# Oxygen_Sensor_CO2_PWM.net
KiCad netlist of a schematic drawn in EAGLE
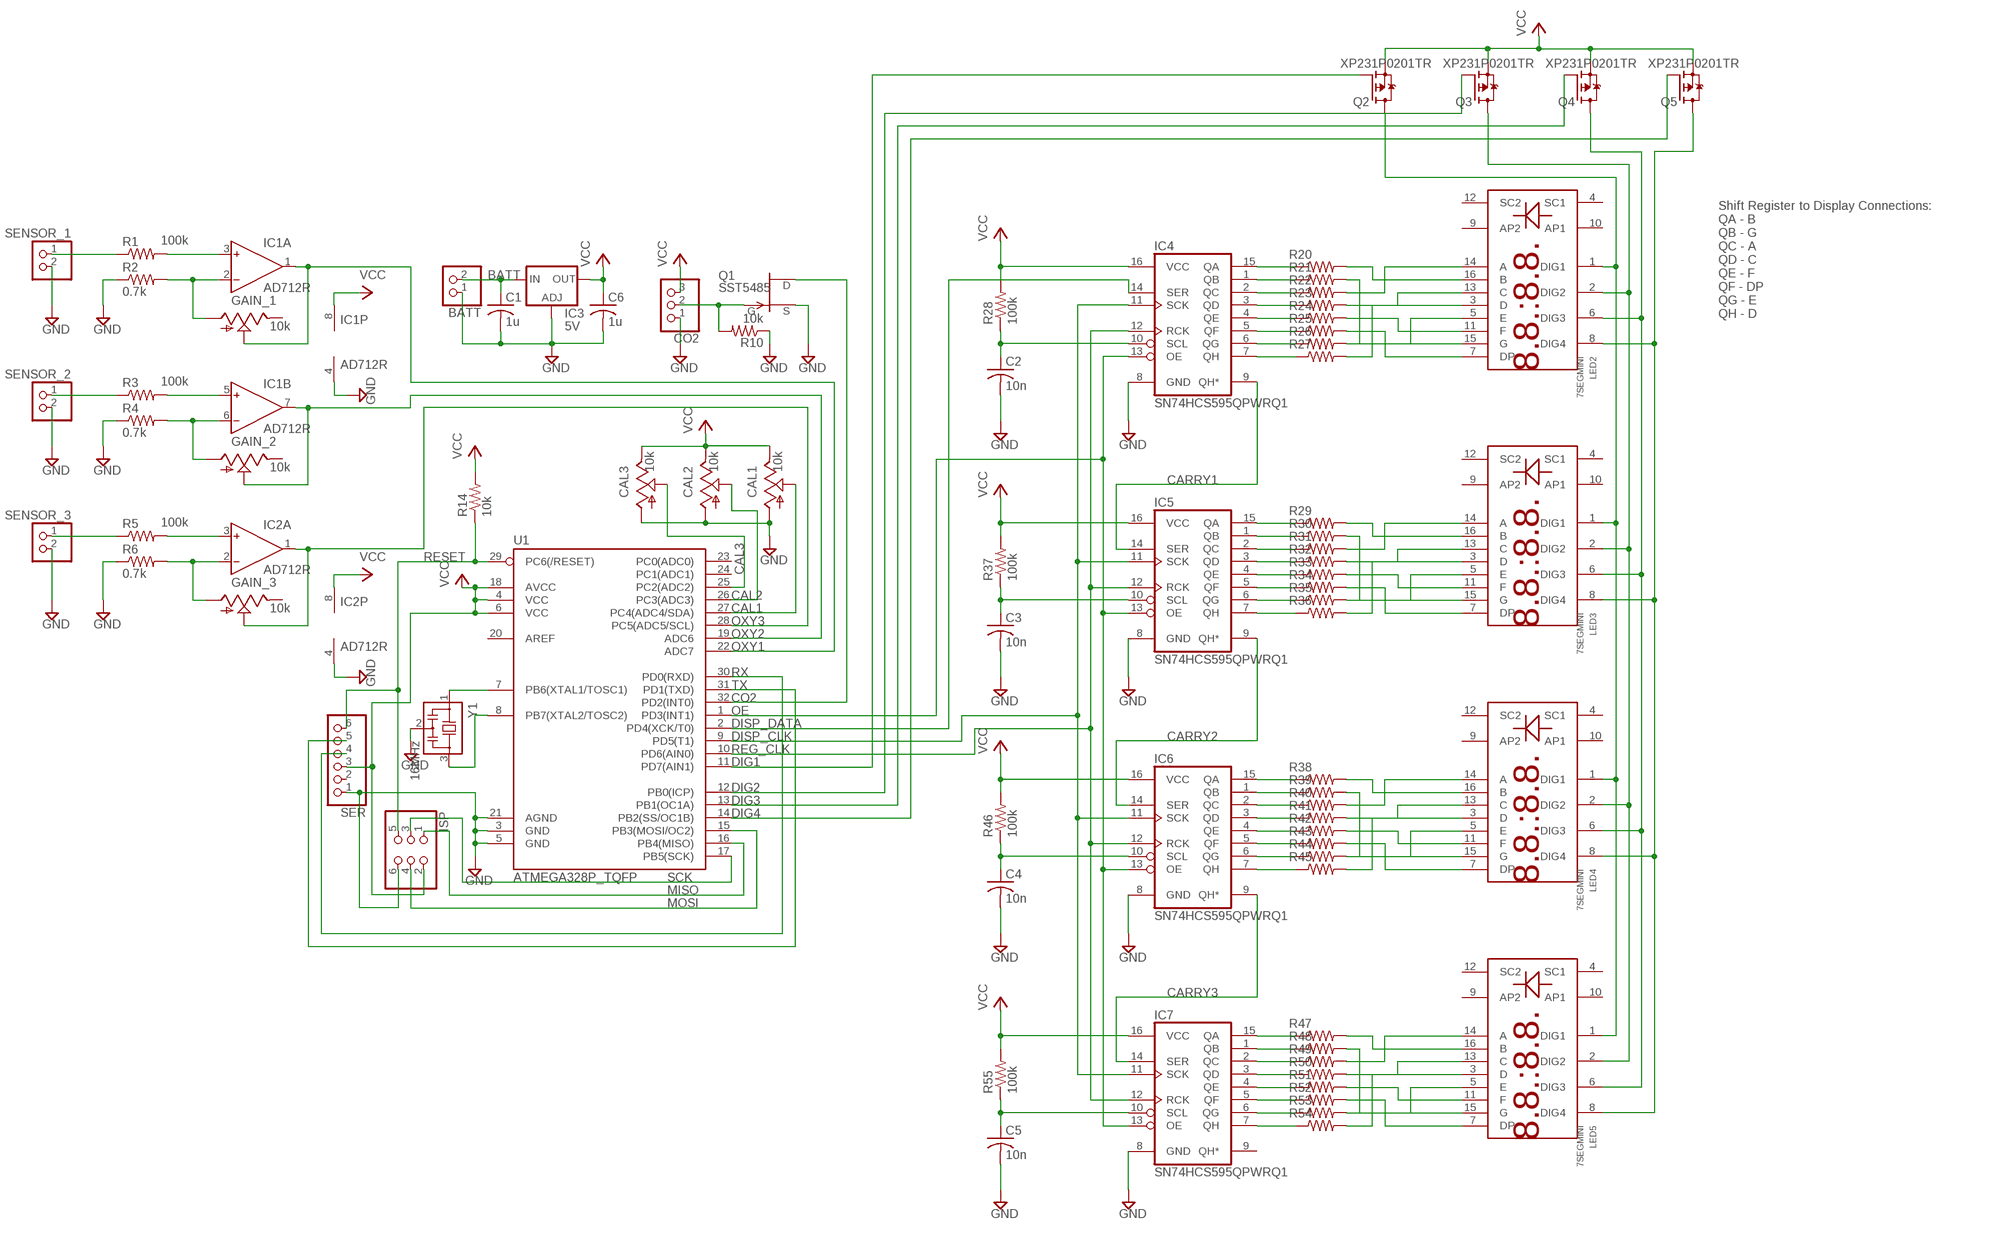
[diagram p0: schematic, sheet 1]

(export (version "E")
  (design (tool "Eeschema 10.0.6"))
  (components
    (comp (ref "BATT")
      (value "BATT")
      (footprint "eagle-import:1X02")
      (libsource (lib "eagle-import") (part "PINHD-1X2"))
    )
    (comp (ref "C1")
      (value "1u")
      (footprint "eagle-import:C0603")
      (libsource (lib "eagle-import") (part "C-USC0603"))
    )
    (comp (ref "C2")
      (value "10n")
      (footprint "eagle-import:C0603")
      (libsource (lib "eagle-import") (part "C-USC0603"))
    )
    (comp (ref "C3")
      (value "10n")
      (footprint "eagle-import:C0603")
      (libsource (lib "eagle-import") (part "C-USC0603"))
    )
    (comp (ref "C4")
      (value "10n")
      (footprint "eagle-import:C0603")
      (libsource (lib "eagle-import") (part "C-USC0603"))
    )
    (comp (ref "C5")
      (value "10n")
      (footprint "eagle-import:C0603")
      (libsource (lib "eagle-import") (part "C-USC0603"))
    )
    (comp (ref "C6")
      (value "1u")
      (footprint "eagle-import:C0603")
      (libsource (lib "eagle-import") (part "C-USC0603"))
    )
    (comp (ref "CAL1")
      (value "10k")
      (footprint "eagle-import:RJ9W")
      (libsource (lib "eagle-import") (part "TRIM_US-RJ9W"))
    )
    (comp (ref "CAL2")
      (value "10k")
      (footprint "eagle-import:RJ9W")
      (libsource (lib "eagle-import") (part "TRIM_US-RJ9W"))
    )
    (comp (ref "CAL3")
      (value "10k")
      (footprint "eagle-import:RJ9W")
      (libsource (lib "eagle-import") (part "TRIM_US-RJ9W"))
    )
    (comp (ref "CO2")
      (value "CO2")
      (footprint "eagle-import:1X03")
      (libsource (lib "eagle-import") (part "PINHD-1X3"))
    )
    (comp (ref "GAIN_1")
      (value "10k")
      (footprint "eagle-import:RJ9W")
      (libsource (lib "eagle-import") (part "TRIM_US-RJ9W"))
    )
    (comp (ref "GAIN_2")
      (value "10k")
      (footprint "eagle-import:RJ9W")
      (libsource (lib "eagle-import") (part "TRIM_US-RJ9W"))
    )
    (comp (ref "GAIN_3")
      (value "10k")
      (footprint "eagle-import:RJ9W")
      (libsource (lib "eagle-import") (part "TRIM_US-RJ9W"))
    )
    (comp (ref "IC1")
      (value "AD712R")
      (footprint "eagle-import:SO8")
      (fields (field (name "MF") "ALTERA CORPORATION") (field (name "MPN") "AD712KRZ"))
      (libsource (lib "eagle-import") (part "AD712R"))
    )
    (comp (ref "IC2")
      (value "AD712R")
      (footprint "eagle-import:SO8")
      (fields (field (name "MF") "ALTERA CORPORATION") (field (name "MPN") "AD712KRZ"))
      (libsource (lib "eagle-import") (part "AD712R"))
    )
    (comp (ref "IC3")
      (value "5V")
      (footprint "eagle-import:SOT223")
      (libsource (lib "eagle-import") (part "LD117A?STR"))
    )
    (comp (ref "IC4")
      (value "SN74HCS595QPWRQ1")
      (footprint "eagle-import:TSSOP16")
      (libsource (lib "eagle-import") (part "SN74HCS595QPWRQ1"))
    )
    (comp (ref "IC5")
      (value "SN74HCS595QPWRQ1")
      (footprint "eagle-import:TSSOP16")
      (libsource (lib "eagle-import") (part "SN74HCS595QPWRQ1"))
    )
    (comp (ref "IC6")
      (value "SN74HCS595QPWRQ1")
      (footprint "eagle-import:TSSOP16")
      (libsource (lib "eagle-import") (part "SN74HCS595QPWRQ1"))
    )
    (comp (ref "IC7")
      (value "SN74HCS595QPWRQ1")
      (footprint "eagle-import:TSSOP16")
      (libsource (lib "eagle-import") (part "SN74HCS595QPWRQ1"))
    )
    (comp (ref "ISP")
      (value "ISP")
      (footprint "eagle-import:2X03")
      (libsource (lib "eagle-import") (part "PINHD-2X3"))
    )
    (comp (ref "LED2")
      (value "7SEGMINI")
      (footprint "eagle-import:7SEGMINI")
      (libsource (lib "eagle-import") (part "7SEGMINI"))
    )
    (comp (ref "LED3")
      (value "7SEGMINI")
      (footprint "eagle-import:7SEGMINI")
      (libsource (lib "eagle-import") (part "7SEGMINI"))
    )
    (comp (ref "LED4")
      (value "7SEGMINI")
      (footprint "eagle-import:7SEGMINI")
      (libsource (lib "eagle-import") (part "7SEGMINI"))
    )
    (comp (ref "LED5")
      (value "7SEGMINI")
      (footprint "eagle-import:7SEGMINI")
      (libsource (lib "eagle-import") (part "7SEGMINI"))
    )
    (comp (ref "Q1")
      (value "SST5485")
      (footprint "eagle-import:SOT23")
      (libsource (lib "eagle-import") (part "?548SST5"))
    )
    (comp (ref "Q2")
      (value "XP231P0201TR")
      (footprint "eagle-import:SOT23")
      (libsource (lib "eagle-import") (part "XP231P0201TR"))
    )
    (comp (ref "Q3")
      (value "XP231P0201TR")
      (footprint "eagle-import:SOT23")
      (libsource (lib "eagle-import") (part "XP231P0201TR"))
    )
    (comp (ref "Q4")
      (value "XP231P0201TR")
      (footprint "eagle-import:SOT23")
      (libsource (lib "eagle-import") (part "XP231P0201TR"))
    )
    (comp (ref "Q5")
      (value "XP231P0201TR")
      (footprint "eagle-import:SOT23")
      (libsource (lib "eagle-import") (part "XP231P0201TR"))
    )
    (comp (ref "R1")
      (value "100k")
      (footprint "eagle-import:R0603")
      (libsource (lib "eagle-import") (part "R-US_R0603"))
    )
    (comp (ref "R2")
      (value "0.7k")
      (footprint "eagle-import:R0603")
      (libsource (lib "eagle-import") (part "R-US_R0603"))
    )
    (comp (ref "R3")
      (value "100k")
      (footprint "eagle-import:R0603")
      (libsource (lib "eagle-import") (part "R-US_R0603"))
    )
    (comp (ref "R4")
      (value "0.7k")
      (footprint "eagle-import:R0603")
      (libsource (lib "eagle-import") (part "R-US_R0603"))
    )
    (comp (ref "R5")
      (value "100k")
      (footprint "eagle-import:R0603")
      (libsource (lib "eagle-import") (part "R-US_R0603"))
    )
    (comp (ref "R6")
      (value "0.7k")
      (footprint "eagle-import:R0603")
      (libsource (lib "eagle-import") (part "R-US_R0603"))
    )
    (comp (ref "R10")
      (value "10k")
      (footprint "eagle-import:R0603")
      (libsource (lib "eagle-import") (part "R-US_R0603"))
    )
    (comp (ref "R14")
      (value "10k")
      (footprint "eagle-import:R0603")
      (libsource (lib "eagle-import") (part "R-US_R0603"))
    )
    (comp (ref "R20")
      (value "R-US_R0603")
      (footprint "eagle-import:R0603")
      (libsource (lib "eagle-import") (part "R-US_R0603"))
    )
    (comp (ref "R21")
      (value "R-US_R0603")
      (footprint "eagle-import:R0603")
      (libsource (lib "eagle-import") (part "R-US_R0603"))
    )
    (comp (ref "R22")
      (value "R-US_R0603")
      (footprint "eagle-import:R0603")
      (libsource (lib "eagle-import") (part "R-US_R0603"))
    )
    (comp (ref "R23")
      (value "R-US_R0603")
      (footprint "eagle-import:R0603")
      (libsource (lib "eagle-import") (part "R-US_R0603"))
    )
    (comp (ref "R24")
      (value "R-US_R0603")
      (footprint "eagle-import:R0603")
      (libsource (lib "eagle-import") (part "R-US_R0603"))
    )
    (comp (ref "R25")
      (value "R-US_R0603")
      (footprint "eagle-import:R0603")
      (libsource (lib "eagle-import") (part "R-US_R0603"))
    )
    (comp (ref "R26")
      (value "R-US_R0603")
      (footprint "eagle-import:R0603")
      (libsource (lib "eagle-import") (part "R-US_R0603"))
    )
    (comp (ref "R27")
      (value "R-US_R0603")
      (footprint "eagle-import:R0603")
      (libsource (lib "eagle-import") (part "R-US_R0603"))
    )
    (comp (ref "R28")
      (value "100k")
      (footprint "eagle-import:R0603")
      (libsource (lib "eagle-import") (part "R-US_R0603"))
    )
    (comp (ref "R29")
      (value "R-US_R0603")
      (footprint "eagle-import:R0603")
      (libsource (lib "eagle-import") (part "R-US_R0603"))
    )
    (comp (ref "R30")
      (value "R-US_R0603")
      (footprint "eagle-import:R0603")
      (libsource (lib "eagle-import") (part "R-US_R0603"))
    )
    (comp (ref "R31")
      (value "R-US_R0603")
      (footprint "eagle-import:R0603")
      (libsource (lib "eagle-import") (part "R-US_R0603"))
    )
    (comp (ref "R32")
      (value "R-US_R0603")
      (footprint "eagle-import:R0603")
      (libsource (lib "eagle-import") (part "R-US_R0603"))
    )
    (comp (ref "R33")
      (value "R-US_R0603")
      (footprint "eagle-import:R0603")
      (libsource (lib "eagle-import") (part "R-US_R0603"))
    )
    (comp (ref "R34")
      (value "R-US_R0603")
      (footprint "eagle-import:R0603")
      (libsource (lib "eagle-import") (part "R-US_R0603"))
    )
    (comp (ref "R35")
      (value "R-US_R0603")
      (footprint "eagle-import:R0603")
      (libsource (lib "eagle-import") (part "R-US_R0603"))
    )
    (comp (ref "R36")
      (value "R-US_R0603")
      (footprint "eagle-import:R0603")
      (libsource (lib "eagle-import") (part "R-US_R0603"))
    )
    (comp (ref "R37")
      (value "100k")
      (footprint "eagle-import:R0603")
      (libsource (lib "eagle-import") (part "R-US_R0603"))
    )
    (comp (ref "R38")
      (value "R-US_R0603")
      (footprint "eagle-import:R0603")
      (libsource (lib "eagle-import") (part "R-US_R0603"))
    )
    (comp (ref "R39")
      (value "R-US_R0603")
      (footprint "eagle-import:R0603")
      (libsource (lib "eagle-import") (part "R-US_R0603"))
    )
    (comp (ref "R40")
      (value "R-US_R0603")
      (footprint "eagle-import:R0603")
      (libsource (lib "eagle-import") (part "R-US_R0603"))
    )
    (comp (ref "R41")
      (value "R-US_R0603")
      (footprint "eagle-import:R0603")
      (libsource (lib "eagle-import") (part "R-US_R0603"))
    )
    (comp (ref "R42")
      (value "R-US_R0603")
      (footprint "eagle-import:R0603")
      (libsource (lib "eagle-import") (part "R-US_R0603"))
    )
    (comp (ref "R43")
      (value "R-US_R0603")
      (footprint "eagle-import:R0603")
      (libsource (lib "eagle-import") (part "R-US_R0603"))
    )
    (comp (ref "R44")
      (value "R-US_R0603")
      (footprint "eagle-import:R0603")
      (libsource (lib "eagle-import") (part "R-US_R0603"))
    )
    (comp (ref "R45")
      (value "R-US_R0603")
      (footprint "eagle-import:R0603")
      (libsource (lib "eagle-import") (part "R-US_R0603"))
    )
    (comp (ref "R46")
      (value "100k")
      (footprint "eagle-import:R0603")
      (libsource (lib "eagle-import") (part "R-US_R0603"))
    )
    (comp (ref "R47")
      (value "R-US_R0603")
      (footprint "eagle-import:R0603")
      (libsource (lib "eagle-import") (part "R-US_R0603"))
    )
    (comp (ref "R48")
      (value "R-US_R0603")
      (footprint "eagle-import:R0603")
      (libsource (lib "eagle-import") (part "R-US_R0603"))
    )
    (comp (ref "R49")
      (value "R-US_R0603")
      (footprint "eagle-import:R0603")
      (libsource (lib "eagle-import") (part "R-US_R0603"))
    )
    (comp (ref "R50")
      (value "R-US_R0603")
      (footprint "eagle-import:R0603")
      (libsource (lib "eagle-import") (part "R-US_R0603"))
    )
    (comp (ref "R51")
      (value "R-US_R0603")
      (footprint "eagle-import:R0603")
      (libsource (lib "eagle-import") (part "R-US_R0603"))
    )
    (comp (ref "R52")
      (value "R-US_R0603")
      (footprint "eagle-import:R0603")
      (libsource (lib "eagle-import") (part "R-US_R0603"))
    )
    (comp (ref "R53")
      (value "R-US_R0603")
      (footprint "eagle-import:R0603")
      (libsource (lib "eagle-import") (part "R-US_R0603"))
    )
    (comp (ref "R54")
      (value "R-US_R0603")
      (footprint "eagle-import:R0603")
      (libsource (lib "eagle-import") (part "R-US_R0603"))
    )
    (comp (ref "R55")
      (value "100k")
      (footprint "eagle-import:R0603")
      (libsource (lib "eagle-import") (part "R-US_R0603"))
    )
    (comp (ref "SENSOR_1")
      (value "PINHD-1X2")
      (footprint "eagle-import:1X02")
      (libsource (lib "eagle-import") (part "PINHD-1X2"))
    )
    (comp (ref "SENSOR_2")
      (value "PINHD-1X2")
      (footprint "eagle-import:1X02")
      (libsource (lib "eagle-import") (part "PINHD-1X2"))
    )
    (comp (ref "SENSOR_3")
      (value "PINHD-1X2")
      (footprint "eagle-import:1X02")
      (libsource (lib "eagle-import") (part "PINHD-1X2"))
    )
    (comp (ref "SER")
      (value "SER")
      (footprint "eagle-import:1X06")
      (libsource (lib "eagle-import") (part "PINHD-1X6"))
    )
    (comp (ref "U1")
      (value "ATMEGA328P_TQFP")
      (footprint "eagle-import:TQFP32-08")
      (libsource (lib "eagle-import") (part "ATMEGA328P_TQFP"))
    )
    (comp (ref "Y1")
      (value "16MHz")
      (footprint "eagle-import:CSTCR6M")
      (libsource (lib "eagle-import") (part "CSTNE16M0V530000R0"))
    )
  )
  (nets
    (net (code "1") (name "/BATT") (class "Default")
      (node (ref "BATT") (pin "2") (pinfunction "2_2") (pintype "passive"))
      (node (ref "C1") (pin "1") (pinfunction "1_1") (pintype "passive"))
      (node (ref "IC3") (pin "3") (pinfunction "IN_3") (pintype "input"))
    )
    (net (code "2") (name "/CAL1") (class "Default")
      (node (ref "CAL1") (pin "S") (pinfunction "S_S") (pintype "passive"))
      (node (ref "U1") (pin "27") (pinfunction "PC4(ADC4/SDA)_27") (pintype "bidirectional"))
    )
    (net (code "3") (name "/CAL2") (class "Default")
      (node (ref "CAL2") (pin "S") (pinfunction "S_S") (pintype "passive"))
      (node (ref "U1") (pin "26") (pinfunction "PC3(ADC3)_26") (pintype "bidirectional"))
    )
    (net (code "4") (name "/CAL3") (class "Default")
      (node (ref "CAL3") (pin "S") (pinfunction "S_S") (pintype "passive"))
      (node (ref "U1") (pin "25") (pinfunction "PC2(ADC2)_25") (pintype "bidirectional"))
    )
    (net (code "5") (name "/CARRY1") (class "Default")
      (node (ref "IC4") (pin "9") (pinfunction "QH*_9") (pintype "tri_state"))
      (node (ref "IC5") (pin "14") (pinfunction "SER_14") (pintype "input"))
    )
    (net (code "6") (name "/CARRY2") (class "Default")
      (node (ref "IC5") (pin "9") (pinfunction "QH*_9") (pintype "tri_state"))
      (node (ref "IC6") (pin "14") (pinfunction "SER_14") (pintype "input"))
    )
    (net (code "7") (name "/CARRY3") (class "Default")
      (node (ref "IC6") (pin "9") (pinfunction "QH*_9") (pintype "tri_state"))
      (node (ref "IC7") (pin "14") (pinfunction "SER_14") (pintype "input"))
    )
    (net (code "8") (name "/CO2") (class "Default")
      (node (ref "Q1") (pin "1") (pinfunction "D_1") (pintype "passive"))
      (node (ref "U1") (pin "32") (pinfunction "PD2(INT0)_32") (pintype "bidirectional"))
    )
    (net (code "9") (name "/DIG1") (class "Default")
      (node (ref "Q2") (pin "1") (pinfunction "G_1") (pintype "passive"))
      (node (ref "U1") (pin "11") (pinfunction "PD7(AIN1)_11") (pintype "bidirectional"))
    )
    (net (code "10") (name "/DIG2") (class "Default")
      (node (ref "Q3") (pin "1") (pinfunction "G_1") (pintype "passive"))
      (node (ref "U1") (pin "12") (pinfunction "PB0(ICP)_12") (pintype "bidirectional"))
    )
    (net (code "11") (name "/DIG3") (class "Default")
      (node (ref "Q4") (pin "1") (pinfunction "G_1") (pintype "passive"))
      (node (ref "U1") (pin "13") (pinfunction "PB1(OC1A)_13") (pintype "bidirectional"))
    )
    (net (code "12") (name "/DIG4") (class "Default")
      (node (ref "Q5") (pin "1") (pinfunction "G_1") (pintype "passive"))
      (node (ref "U1") (pin "14") (pinfunction "PB2(SS/OC1B)_14") (pintype "bidirectional"))
    )
    (net (code "13") (name "/DISP_CLK") (class "Default")
      (node (ref "IC4") (pin "11") (pinfunction "SCK_11") (pintype "input"))
      (node (ref "IC5") (pin "11") (pinfunction "SCK_11") (pintype "input"))
      (node (ref "IC6") (pin "11") (pinfunction "SCK_11") (pintype "input"))
      (node (ref "IC7") (pin "11") (pinfunction "SCK_11") (pintype "input"))
      (node (ref "U1") (pin "9") (pinfunction "PD5(T1)_9") (pintype "bidirectional"))
    )
    (net (code "14") (name "/DISP_DATA") (class "Default")
      (node (ref "IC4") (pin "14") (pinfunction "SER_14") (pintype "input"))
      (node (ref "U1") (pin "2") (pinfunction "PD4(XCK/T0)_2") (pintype "bidirectional"))
    )
    (net (code "15") (name "/MISO") (class "Default")
      (node (ref "ISP") (pin "1") (pinfunction "1_1") (pintype "passive"))
      (node (ref "U1") (pin "16") (pinfunction "PB4(MISO)_16") (pintype "bidirectional"))
    )
    (net (code "16") (name "/MOSI") (class "Default")
      (node (ref "ISP") (pin "4") (pinfunction "4_4") (pintype "passive"))
      (node (ref "U1") (pin "15") (pinfunction "PB3(MOSI/OC2)_15") (pintype "bidirectional"))
    )
    (net (code "17") (name "/OE") (class "Default")
      (node (ref "IC4") (pin "13") (pinfunction "OE_13") (pintype "bidirectional"))
      (node (ref "IC5") (pin "13") (pinfunction "OE_13") (pintype "bidirectional"))
      (node (ref "IC6") (pin "13") (pinfunction "OE_13") (pintype "bidirectional"))
      (node (ref "IC7") (pin "13") (pinfunction "OE_13") (pintype "bidirectional"))
      (node (ref "U1") (pin "1") (pinfunction "PD3(INT1)_1") (pintype "bidirectional"))
    )
    (net (code "18") (name "/OXY1") (class "Default")
      (node (ref "GAIN_1") (pin "S") (pinfunction "S_S") (pintype "passive"))
      (node (ref "IC1") (pin "1") (pinfunction "OUT_1") (pintype "output"))
      (node (ref "U1") (pin "22") (pinfunction "ADC7_22") (pintype "bidirectional"))
    )
    (net (code "19") (name "/OXY2") (class "Default")
      (node (ref "GAIN_2") (pin "S") (pinfunction "S_S") (pintype "passive"))
      (node (ref "IC1") (pin "7") (pinfunction "OUT_7") (pintype "output"))
      (node (ref "U1") (pin "19") (pinfunction "ADC6_19") (pintype "bidirectional"))
    )
    (net (code "20") (name "/OXY3") (class "Default")
      (node (ref "GAIN_3") (pin "S") (pinfunction "S_S") (pintype "passive"))
      (node (ref "IC2") (pin "1") (pinfunction "OUT_1") (pintype "output"))
      (node (ref "U1") (pin "28") (pinfunction "PC5(ADC5/SCL)_28") (pintype "bidirectional"))
    )
    (net (code "21") (name "/REG_CLK") (class "Default")
      (node (ref "IC4") (pin "12") (pinfunction "RCK_12") (pintype "input"))
      (node (ref "IC5") (pin "12") (pinfunction "RCK_12") (pintype "input"))
      (node (ref "IC6") (pin "12") (pinfunction "RCK_12") (pintype "input"))
      (node (ref "IC7") (pin "12") (pinfunction "RCK_12") (pintype "input"))
      (node (ref "U1") (pin "10") (pinfunction "PD6(AIN0)_10") (pintype "bidirectional"))
    )
    (net (code "22") (name "/RESET") (class "Default")
      (node (ref "ISP") (pin "5") (pinfunction "5_5") (pintype "passive"))
      (node (ref "R14") (pin "1") (pinfunction "1_1") (pintype "passive"))
      (node (ref "SER") (pin "6") (pinfunction "6_6") (pintype "passive"))
      (node (ref "U1") (pin "29") (pinfunction "PC6(/RESET)_29") (pintype "bidirectional"))
    )
    (net (code "23") (name "/RX") (class "Default")
      (node (ref "SER") (pin "4") (pinfunction "4_4") (pintype "passive"))
      (node (ref "U1") (pin "30") (pinfunction "PD0(RXD)_30") (pintype "bidirectional"))
    )
    (net (code "24") (name "/SCK") (class "Default")
      (node (ref "ISP") (pin "3") (pinfunction "3_3") (pintype "passive"))
      (node (ref "U1") (pin "17") (pinfunction "PB5(SCK)_17") (pintype "bidirectional"))
    )
    (net (code "25") (name "/TX") (class "Default")
      (node (ref "SER") (pin "5") (pinfunction "5_5") (pintype "passive"))
      (node (ref "U1") (pin "31") (pinfunction "PD1(TXD)_31") (pintype "bidirectional"))
    )
    (net (code "26") (name "GND") (class "Default")
      (node (ref "BATT") (pin "1") (pinfunction "1_1") (pintype "passive"))
      (node (ref "C1") (pin "2") (pinfunction "2_2") (pintype "passive"))
      (node (ref "C2") (pin "2") (pinfunction "2_2") (pintype "passive"))
      (node (ref "C3") (pin "2") (pinfunction "2_2") (pintype "passive"))
      (node (ref "C4") (pin "2") (pinfunction "2_2") (pintype "passive"))
      (node (ref "C5") (pin "2") (pinfunction "2_2") (pintype "passive"))
      (node (ref "C6") (pin "2") (pinfunction "2_2") (pintype "passive"))
      (node (ref "CAL1") (pin "A") (pinfunction "A_A") (pintype "passive"))
      (node (ref "CAL2") (pin "A") (pinfunction "A_A") (pintype "passive"))
      (node (ref "CAL3") (pin "A") (pinfunction "A_A") (pintype "passive"))
      (node (ref "CO2") (pin "1") (pinfunction "1_1") (pintype "passive"))
      (node (ref "IC1") (pin "4") (pinfunction "V-_4") (pintype "power_in"))
      (node (ref "IC2") (pin "4") (pinfunction "V-_4") (pintype "power_in"))
      (node (ref "IC3") (pin "1") (pinfunction "ADJ_1") (pintype "input"))
      (node (ref "IC4") (pin "8") (pinfunction "GND_8") (pintype "power_in"))
      (node (ref "IC5") (pin "8") (pinfunction "GND_8") (pintype "power_in"))
      (node (ref "IC6") (pin "8") (pinfunction "GND_8") (pintype "power_in"))
      (node (ref "IC7") (pin "8") (pinfunction "GND_8") (pintype "power_in"))
      (node (ref "ISP") (pin "6") (pinfunction "6_6") (pintype "passive"))
      (node (ref "Q1") (pin "2") (pinfunction "S_2") (pintype "passive"))
      (node (ref "R10") (pin "1") (pinfunction "1_1") (pintype "passive"))
      (node (ref "R2") (pin "1") (pinfunction "1_1") (pintype "passive"))
      (node (ref "R4") (pin "1") (pinfunction "1_1") (pintype "passive"))
      (node (ref "R6") (pin "1") (pinfunction "1_1") (pintype "passive"))
      (node (ref "SENSOR_1") (pin "2") (pinfunction "2_2") (pintype "passive"))
      (node (ref "SENSOR_2") (pin "2") (pinfunction "2_2") (pintype "passive"))
      (node (ref "SENSOR_3") (pin "2") (pinfunction "2_2") (pintype "passive"))
      (node (ref "SER") (pin "1") (pinfunction "1_1") (pintype "passive"))
      (node (ref "U1") (pin "21") (pinfunction "AGND_21") (pintype "bidirectional"))
      (node (ref "U1") (pin "3") (pinfunction "GND_3") (pintype "bidirectional"))
      (node (ref "U1") (pin "5") (pinfunction "GND_5") (pintype "bidirectional"))
      (node (ref "Y1") (pin "2") (pinfunction "2_2") (pintype "passive"))
    )
    (net (code "27") (name "Net-(IC1A-IN+)") (class "Default")
      (node (ref "IC1") (pin "3") (pinfunction "IN+_3") (pintype "input"))
      (node (ref "R1") (pin "2") (pinfunction "2_2") (pintype "passive"))
    )
    (net (code "28") (name "Net-(IC1A-IN-)") (class "Default")
      (node (ref "GAIN_1") (pin "A") (pinfunction "A_A") (pintype "passive"))
      (node (ref "IC1") (pin "2") (pinfunction "IN-_2") (pintype "input"))
      (node (ref "R2") (pin "2") (pinfunction "2_2") (pintype "passive"))
    )
    (net (code "29") (name "Net-(IC1B-IN+)") (class "Default")
      (node (ref "IC1") (pin "5") (pinfunction "IN+_5") (pintype "input"))
      (node (ref "R3") (pin "2") (pinfunction "2_2") (pintype "passive"))
    )
    (net (code "30") (name "Net-(IC1B-IN-)") (class "Default")
      (node (ref "GAIN_2") (pin "A") (pinfunction "A_A") (pintype "passive"))
      (node (ref "IC1") (pin "6") (pinfunction "IN-_6") (pintype "input"))
      (node (ref "R4") (pin "2") (pinfunction "2_2") (pintype "passive"))
    )
    (net (code "31") (name "Net-(IC2A-IN+)") (class "Default")
      (node (ref "IC2") (pin "3") (pinfunction "IN+_3") (pintype "input"))
      (node (ref "R5") (pin "2") (pinfunction "2_2") (pintype "passive"))
    )
    (net (code "32") (name "Net-(IC2A-IN-)") (class "Default")
      (node (ref "GAIN_3") (pin "A") (pinfunction "A_A") (pintype "passive"))
      (node (ref "IC2") (pin "2") (pinfunction "IN-_2") (pintype "input"))
      (node (ref "R6") (pin "2") (pinfunction "2_2") (pintype "passive"))
    )
    (net (code "33") (name "Net-(IC4-QA)") (class "Default")
      (node (ref "IC4") (pin "15") (pinfunction "QA_15") (pintype "tri_state"))
      (node (ref "R20") (pin "1") (pinfunction "1_1") (pintype "passive"))
    )
    (net (code "34") (name "Net-(IC4-QB)") (class "Default")
      (node (ref "IC4") (pin "1") (pinfunction "QB_1") (pintype "tri_state"))
      (node (ref "R21") (pin "1") (pinfunction "1_1") (pintype "passive"))
    )
    (net (code "35") (name "Net-(IC4-QC)") (class "Default")
      (node (ref "IC4") (pin "2") (pinfunction "QC_2") (pintype "tri_state"))
      (node (ref "R22") (pin "1") (pinfunction "1_1") (pintype "passive"))
    )
    (net (code "36") (name "Net-(IC4-QD)") (class "Default")
      (node (ref "IC4") (pin "3") (pinfunction "QD_3") (pintype "tri_state"))
      (node (ref "R23") (pin "1") (pinfunction "1_1") (pintype "passive"))
    )
    (net (code "37") (name "Net-(IC4-QE)") (class "Default")
      (node (ref "IC4") (pin "4") (pinfunction "QE_4") (pintype "tri_state"))
      (node (ref "R24") (pin "1") (pinfunction "1_1") (pintype "passive"))
    )
    (net (code "38") (name "Net-(IC4-QF)") (class "Default")
      (node (ref "IC4") (pin "5") (pinfunction "QF_5") (pintype "tri_state"))
      (node (ref "R25") (pin "1") (pinfunction "1_1") (pintype "passive"))
    )
    (net (code "39") (name "Net-(IC4-QG)") (class "Default")
      (node (ref "IC4") (pin "6") (pinfunction "QG_6") (pintype "tri_state"))
      (node (ref "R26") (pin "1") (pinfunction "1_1") (pintype "passive"))
    )
    (net (code "40") (name "Net-(IC4-QH)") (class "Default")
      (node (ref "IC4") (pin "7") (pinfunction "QH_7") (pintype "tri_state"))
      (node (ref "R27") (pin "1") (pinfunction "1_1") (pintype "passive"))
    )
    (net (code "41") (name "Net-(IC4-SCL)") (class "Default")
      (node (ref "C2") (pin "1") (pinfunction "1_1") (pintype "passive"))
      (node (ref "IC4") (pin "10") (pinfunction "SCL_10") (pintype "input"))
      (node (ref "R28") (pin "1") (pinfunction "1_1") (pintype "passive"))
    )
    (net (code "42") (name "Net-(IC5-QA)") (class "Default")
      (node (ref "IC5") (pin "15") (pinfunction "QA_15") (pintype "tri_state"))
      (node (ref "R29") (pin "1") (pinfunction "1_1") (pintype "passive"))
    )
    (net (code "43") (name "Net-(IC5-QB)") (class "Default")
      (node (ref "IC5") (pin "1") (pinfunction "QB_1") (pintype "tri_state"))
      (node (ref "R30") (pin "1") (pinfunction "1_1") (pintype "passive"))
    )
    (net (code "44") (name "Net-(IC5-QC)") (class "Default")
      (node (ref "IC5") (pin "2") (pinfunction "QC_2") (pintype "tri_state"))
      (node (ref "R31") (pin "1") (pinfunction "1_1") (pintype "passive"))
    )
    (net (code "45") (name "Net-(IC5-QD)") (class "Default")
      (node (ref "IC5") (pin "3") (pinfunction "QD_3") (pintype "tri_state"))
      (node (ref "R32") (pin "1") (pinfunction "1_1") (pintype "passive"))
    )
    (net (code "46") (name "Net-(IC5-QE)") (class "Default")
      (node (ref "IC5") (pin "4") (pinfunction "QE_4") (pintype "tri_state"))
      (node (ref "R33") (pin "1") (pinfunction "1_1") (pintype "passive"))
    )
    (net (code "47") (name "Net-(IC5-QF)") (class "Default")
      (node (ref "IC5") (pin "5") (pinfunction "QF_5") (pintype "tri_state"))
      (node (ref "R34") (pin "1") (pinfunction "1_1") (pintype "passive"))
    )
    (net (code "48") (name "Net-(IC5-QG)") (class "Default")
      (node (ref "IC5") (pin "6") (pinfunction "QG_6") (pintype "tri_state"))
      (node (ref "R35") (pin "1") (pinfunction "1_1") (pintype "passive"))
    )
    (net (code "49") (name "Net-(IC5-QH)") (class "Default")
      (node (ref "IC5") (pin "7") (pinfunction "QH_7") (pintype "tri_state"))
      (node (ref "R36") (pin "1") (pinfunction "1_1") (pintype "passive"))
    )
    (net (code "50") (name "Net-(IC5-SCL)") (class "Default")
      (node (ref "C3") (pin "1") (pinfunction "1_1") (pintype "passive"))
      (node (ref "IC5") (pin "10") (pinfunction "SCL_10") (pintype "input"))
      (node (ref "R37") (pin "1") (pinfunction "1_1") (pintype "passive"))
    )
    (net (code "51") (name "Net-(IC6-QA)") (class "Default")
      (node (ref "IC6") (pin "15") (pinfunction "QA_15") (pintype "tri_state"))
      (node (ref "R38") (pin "1") (pinfunction "1_1") (pintype "passive"))
    )
    (net (code "52") (name "Net-(IC6-QB)") (class "Default")
      (node (ref "IC6") (pin "1") (pinfunction "QB_1") (pintype "tri_state"))
      (node (ref "R39") (pin "1") (pinfunction "1_1") (pintype "passive"))
    )
    (net (code "53") (name "Net-(IC6-QC)") (class "Default")
      (node (ref "IC6") (pin "2") (pinfunction "QC_2") (pintype "tri_state"))
      (node (ref "R40") (pin "1") (pinfunction "1_1") (pintype "passive"))
    )
    (net (code "54") (name "Net-(IC6-QD)") (class "Default")
      (node (ref "IC6") (pin "3") (pinfunction "QD_3") (pintype "tri_state"))
      (node (ref "R41") (pin "1") (pinfunction "1_1") (pintype "passive"))
    )
    (net (code "55") (name "Net-(IC6-QE)") (class "Default")
      (node (ref "IC6") (pin "4") (pinfunction "QE_4") (pintype "tri_state"))
      (node (ref "R42") (pin "1") (pinfunction "1_1") (pintype "passive"))
    )
    (net (code "56") (name "Net-(IC6-QF)") (class "Default")
      (node (ref "IC6") (pin "5") (pinfunction "QF_5") (pintype "tri_state"))
      (node (ref "R43") (pin "1") (pinfunction "1_1") (pintype "passive"))
    )
    (net (code "57") (name "Net-(IC6-QG)") (class "Default")
      (node (ref "IC6") (pin "6") (pinfunction "QG_6") (pintype "tri_state"))
      (node (ref "R44") (pin "1") (pinfunction "1_1") (pintype "passive"))
    )
    (net (code "58") (name "Net-(IC6-QH)") (class "Default")
      (node (ref "IC6") (pin "7") (pinfunction "QH_7") (pintype "tri_state"))
      (node (ref "R45") (pin "1") (pinfunction "1_1") (pintype "passive"))
    )
    (net (code "59") (name "Net-(IC6-SCL)") (class "Default")
      (node (ref "C4") (pin "1") (pinfunction "1_1") (pintype "passive"))
      (node (ref "IC6") (pin "10") (pinfunction "SCL_10") (pintype "input"))
      (node (ref "R46") (pin "1") (pinfunction "1_1") (pintype "passive"))
    )
    (net (code "60") (name "Net-(IC7-QA)") (class "Default")
      (node (ref "IC7") (pin "15") (pinfunction "QA_15") (pintype "tri_state"))
      (node (ref "R47") (pin "1") (pinfunction "1_1") (pintype "passive"))
    )
    (net (code "61") (name "Net-(IC7-QB)") (class "Default")
      (node (ref "IC7") (pin "1") (pinfunction "QB_1") (pintype "tri_state"))
      (node (ref "R48") (pin "1") (pinfunction "1_1") (pintype "passive"))
    )
    (net (code "62") (name "Net-(IC7-QC)") (class "Default")
      (node (ref "IC7") (pin "2") (pinfunction "QC_2") (pintype "tri_state"))
      (node (ref "R49") (pin "1") (pinfunction "1_1") (pintype "passive"))
    )
    (net (code "63") (name "Net-(IC7-QD)") (class "Default")
      (node (ref "IC7") (pin "3") (pinfunction "QD_3") (pintype "tri_state"))
      (node (ref "R50") (pin "1") (pinfunction "1_1") (pintype "passive"))
    )
    (net (code "64") (name "Net-(IC7-QE)") (class "Default")
      (node (ref "IC7") (pin "4") (pinfunction "QE_4") (pintype "tri_state"))
      (node (ref "R51") (pin "1") (pinfunction "1_1") (pintype "passive"))
    )
    (net (code "65") (name "Net-(IC7-QF)") (class "Default")
      (node (ref "IC7") (pin "5") (pinfunction "QF_5") (pintype "tri_state"))
      (node (ref "R52") (pin "1") (pinfunction "1_1") (pintype "passive"))
    )
    (net (code "66") (name "Net-(IC7-QG)") (class "Default")
      (node (ref "IC7") (pin "6") (pinfunction "QG_6") (pintype "tri_state"))
      (node (ref "R53") (pin "1") (pinfunction "1_1") (pintype "passive"))
    )
    (net (code "67") (name "Net-(IC7-QH)") (class "Default")
      (node (ref "IC7") (pin "7") (pinfunction "QH_7") (pintype "tri_state"))
      (node (ref "R54") (pin "1") (pinfunction "1_1") (pintype "passive"))
    )
    (net (code "68") (name "Net-(IC7-SCL)") (class "Default")
      (node (ref "C5") (pin "1") (pinfunction "1_1") (pintype "passive"))
      (node (ref "IC7") (pin "10") (pinfunction "SCL_10") (pintype "input"))
      (node (ref "R55") (pin "1") (pinfunction "1_1") (pintype "passive"))
    )
    (net (code "69") (name "Net-(LED2-A)") (class "Default")
      (node (ref "LED2") (pin "14") (pinfunction "A_14") (pintype "bidirectional"))
      (node (ref "R22") (pin "2") (pinfunction "2_2") (pintype "passive"))
    )
    (net (code "70") (name "Net-(LED2-B)") (class "Default")
      (node (ref "LED2") (pin "16") (pinfunction "B_16") (pintype "bidirectional"))
      (node (ref "R20") (pin "2") (pinfunction "2_2") (pintype "passive"))
    )
    (net (code "71") (name "Net-(LED2-C)") (class "Default")
      (node (ref "LED2") (pin "13") (pinfunction "C_13") (pintype "bidirectional"))
      (node (ref "R23") (pin "2") (pinfunction "2_2") (pintype "passive"))
    )
    (net (code "72") (name "Net-(LED2-D)") (class "Default")
      (node (ref "LED2") (pin "3") (pinfunction "D_3") (pintype "bidirectional"))
      (node (ref "R27") (pin "2") (pinfunction "2_2") (pintype "passive"))
    )
    (net (code "73") (name "Net-(LED2-DIG1)") (class "Default")
      (node (ref "LED2") (pin "1") (pinfunction "DIG1_1") (pintype "bidirectional"))
      (node (ref "LED3") (pin "1") (pinfunction "DIG1_1") (pintype "bidirectional"))
      (node (ref "LED4") (pin "1") (pinfunction "DIG1_1") (pintype "bidirectional"))
      (node (ref "LED5") (pin "1") (pinfunction "DIG1_1") (pintype "bidirectional"))
      (node (ref "Q2") (pin "3") (pinfunction "D_3") (pintype "passive"))
    )
    (net (code "74") (name "Net-(LED2-DIG2)") (class "Default")
      (node (ref "LED2") (pin "2") (pinfunction "DIG2_2") (pintype "bidirectional"))
      (node (ref "LED3") (pin "2") (pinfunction "DIG2_2") (pintype "bidirectional"))
      (node (ref "LED4") (pin "2") (pinfunction "DIG2_2") (pintype "bidirectional"))
      (node (ref "LED5") (pin "2") (pinfunction "DIG2_2") (pintype "bidirectional"))
      (node (ref "Q3") (pin "3") (pinfunction "D_3") (pintype "passive"))
    )
    (net (code "75") (name "Net-(LED2-DIG3)") (class "Default")
      (node (ref "LED2") (pin "6") (pinfunction "DIG3_6") (pintype "bidirectional"))
      (node (ref "LED3") (pin "6") (pinfunction "DIG3_6") (pintype "bidirectional"))
      (node (ref "LED4") (pin "6") (pinfunction "DIG3_6") (pintype "bidirectional"))
      (node (ref "LED5") (pin "6") (pinfunction "DIG3_6") (pintype "bidirectional"))
      (node (ref "Q4") (pin "3") (pinfunction "D_3") (pintype "passive"))
    )
    (net (code "76") (name "Net-(LED2-DIG4)") (class "Default")
      (node (ref "LED2") (pin "8") (pinfunction "DIG4_8") (pintype "bidirectional"))
      (node (ref "LED3") (pin "8") (pinfunction "DIG4_8") (pintype "bidirectional"))
      (node (ref "LED4") (pin "8") (pinfunction "DIG4_8") (pintype "bidirectional"))
      (node (ref "LED5") (pin "8") (pinfunction "DIG4_8") (pintype "bidirectional"))
      (node (ref "Q5") (pin "3") (pinfunction "D_3") (pintype "passive"))
    )
    (net (code "77") (name "Net-(LED2-DP)") (class "Default")
      (node (ref "LED2") (pin "7") (pinfunction "DP_7") (pintype "bidirectional"))
      (node (ref "R25") (pin "2") (pinfunction "2_2") (pintype "passive"))
    )
    (net (code "78") (name "Net-(LED2-E)") (class "Default")
      (node (ref "LED2") (pin "5") (pinfunction "E_5") (pintype "bidirectional"))
      (node (ref "R26") (pin "2") (pinfunction "2_2") (pintype "passive"))
    )
    (net (code "79") (name "Net-(LED2-F)") (class "Default")
      (node (ref "LED2") (pin "11") (pinfunction "F_11") (pintype "bidirectional"))
      (node (ref "R24") (pin "2") (pinfunction "2_2") (pintype "passive"))
    )
    (net (code "80") (name "Net-(LED2-G)") (class "Default")
      (node (ref "LED2") (pin "15") (pinfunction "G_15") (pintype "bidirectional"))
      (node (ref "R21") (pin "2") (pinfunction "2_2") (pintype "passive"))
    )
    (net (code "81") (name "Net-(LED3-A)") (class "Default")
      (node (ref "LED3") (pin "14") (pinfunction "A_14") (pintype "bidirectional"))
      (node (ref "R31") (pin "2") (pinfunction "2_2") (pintype "passive"))
    )
    (net (code "82") (name "Net-(LED3-B)") (class "Default")
      (node (ref "LED3") (pin "16") (pinfunction "B_16") (pintype "bidirectional"))
      (node (ref "R29") (pin "2") (pinfunction "2_2") (pintype "passive"))
    )
    (net (code "83") (name "Net-(LED3-C)") (class "Default")
      (node (ref "LED3") (pin "13") (pinfunction "C_13") (pintype "bidirectional"))
      (node (ref "R32") (pin "2") (pinfunction "2_2") (pintype "passive"))
    )
    (net (code "84") (name "Net-(LED3-D)") (class "Default")
      (node (ref "LED3") (pin "3") (pinfunction "D_3") (pintype "bidirectional"))
      (node (ref "R36") (pin "2") (pinfunction "2_2") (pintype "passive"))
    )
    (net (code "85") (name "Net-(LED3-DP)") (class "Default")
      (node (ref "LED3") (pin "7") (pinfunction "DP_7") (pintype "bidirectional"))
      (node (ref "R34") (pin "2") (pinfunction "2_2") (pintype "passive"))
    )
    (net (code "86") (name "Net-(LED3-E)") (class "Default")
      (node (ref "LED3") (pin "5") (pinfunction "E_5") (pintype "bidirectional"))
      (node (ref "R35") (pin "2") (pinfunction "2_2") (pintype "passive"))
    )
    (net (code "87") (name "Net-(LED3-F)") (class "Default")
      (node (ref "LED3") (pin "11") (pinfunction "F_11") (pintype "bidirectional"))
      (node (ref "R33") (pin "2") (pinfunction "2_2") (pintype "passive"))
    )
    (net (code "88") (name "Net-(LED3-G)") (class "Default")
      (node (ref "LED3") (pin "15") (pinfunction "G_15") (pintype "bidirectional"))
      (node (ref "R30") (pin "2") (pinfunction "2_2") (pintype "passive"))
    )
    (net (code "89") (name "Net-(LED4-A)") (class "Default")
      (node (ref "LED4") (pin "14") (pinfunction "A_14") (pintype "bidirectional"))
      (node (ref "R40") (pin "2") (pinfunction "2_2") (pintype "passive"))
    )
    (net (code "90") (name "Net-(LED4-B)") (class "Default")
      (node (ref "LED4") (pin "16") (pinfunction "B_16") (pintype "bidirectional"))
      (node (ref "R38") (pin "2") (pinfunction "2_2") (pintype "passive"))
    )
    (net (code "91") (name "Net-(LED4-C)") (class "Default")
      (node (ref "LED4") (pin "13") (pinfunction "C_13") (pintype "bidirectional"))
      (node (ref "R41") (pin "2") (pinfunction "2_2") (pintype "passive"))
    )
    (net (code "92") (name "Net-(LED4-D)") (class "Default")
      (node (ref "LED4") (pin "3") (pinfunction "D_3") (pintype "bidirectional"))
      (node (ref "R45") (pin "2") (pinfunction "2_2") (pintype "passive"))
    )
    (net (code "93") (name "Net-(LED4-DP)") (class "Default")
      (node (ref "LED4") (pin "7") (pinfunction "DP_7") (pintype "bidirectional"))
      (node (ref "R43") (pin "2") (pinfunction "2_2") (pintype "passive"))
    )
    (net (code "94") (name "Net-(LED4-E)") (class "Default")
      (node (ref "LED4") (pin "5") (pinfunction "E_5") (pintype "bidirectional"))
      (node (ref "R44") (pin "2") (pinfunction "2_2") (pintype "passive"))
    )
    (net (code "95") (name "Net-(LED4-F)") (class "Default")
      (node (ref "LED4") (pin "11") (pinfunction "F_11") (pintype "bidirectional"))
      (node (ref "R42") (pin "2") (pinfunction "2_2") (pintype "passive"))
    )
    (net (code "96") (name "Net-(LED4-G)") (class "Default")
      (node (ref "LED4") (pin "15") (pinfunction "G_15") (pintype "bidirectional"))
      (node (ref "R39") (pin "2") (pinfunction "2_2") (pintype "passive"))
    )
    (net (code "97") (name "Net-(LED5-A)") (class "Default")
      (node (ref "LED5") (pin "14") (pinfunction "A_14") (pintype "bidirectional"))
      (node (ref "R49") (pin "2") (pinfunction "2_2") (pintype "passive"))
    )
    (net (code "98") (name "Net-(LED5-B)") (class "Default")
      (node (ref "LED5") (pin "16") (pinfunction "B_16") (pintype "bidirectional"))
      (node (ref "R47") (pin "2") (pinfunction "2_2") (pintype "passive"))
    )
    (net (code "99") (name "Net-(LED5-C)") (class "Default")
      (node (ref "LED5") (pin "13") (pinfunction "C_13") (pintype "bidirectional"))
      (node (ref "R50") (pin "2") (pinfunction "2_2") (pintype "passive"))
    )
    (net (code "100") (name "Net-(LED5-D)") (class "Default")
      (node (ref "LED5") (pin "3") (pinfunction "D_3") (pintype "bidirectional"))
      (node (ref "R54") (pin "2") (pinfunction "2_2") (pintype "passive"))
    )
    (net (code "101") (name "Net-(LED5-DP)") (class "Default")
      (node (ref "LED5") (pin "7") (pinfunction "DP_7") (pintype "bidirectional"))
      (node (ref "R52") (pin "2") (pinfunction "2_2") (pintype "passive"))
    )
    (net (code "102") (name "Net-(LED5-E)") (class "Default")
      (node (ref "LED5") (pin "5") (pinfunction "E_5") (pintype "bidirectional"))
      (node (ref "R53") (pin "2") (pinfunction "2_2") (pintype "passive"))
    )
    (net (code "103") (name "Net-(LED5-F)") (class "Default")
      (node (ref "LED5") (pin "11") (pinfunction "F_11") (pintype "bidirectional"))
      (node (ref "R51") (pin "2") (pinfunction "2_2") (pintype "passive"))
    )
    (net (code "104") (name "Net-(LED5-G)") (class "Default")
      (node (ref "LED5") (pin "15") (pinfunction "G_15") (pintype "bidirectional"))
      (node (ref "R48") (pin "2") (pinfunction "2_2") (pintype "passive"))
    )
    (net (code "105") (name "Net-(Q1-G)") (class "Default")
      (node (ref "CO2") (pin "2") (pinfunction "2_2") (pintype "passive"))
      (node (ref "Q1") (pin "3") (pinfunction "G_3") (pintype "passive"))
      (node (ref "R10") (pin "2") (pinfunction "2_2") (pintype "passive"))
    )
    (net (code "106") (name "Net-(R1-Pad1)") (class "Default")
      (node (ref "R1") (pin "1") (pinfunction "1_1") (pintype "passive"))
      (node (ref "SENSOR_1") (pin "1") (pinfunction "1_1") (pintype "passive"))
    )
    (net (code "107") (name "Net-(R3-Pad1)") (class "Default")
      (node (ref "R3") (pin "1") (pinfunction "1_1") (pintype "passive"))
      (node (ref "SENSOR_2") (pin "1") (pinfunction "1_1") (pintype "passive"))
    )
    (net (code "108") (name "Net-(R5-Pad1)") (class "Default")
      (node (ref "R5") (pin "1") (pinfunction "1_1") (pintype "passive"))
      (node (ref "SENSOR_3") (pin "1") (pinfunction "1_1") (pintype "passive"))
    )
    (net (code "109") (name "Net-(U1-PB6(XTAL1{slash}TOSC1))") (class "Default")
      (node (ref "U1") (pin "7") (pinfunction "PB6(XTAL1/TOSC1)_7") (pintype "bidirectional"))
      (node (ref "Y1") (pin "1") (pinfunction "1_1") (pintype "passive"))
    )
    (net (code "110") (name "Net-(U1-PB7(XTAL2{slash}TOSC2))") (class "Default")
      (node (ref "U1") (pin "8") (pinfunction "PB7(XTAL2/TOSC2)_8") (pintype "bidirectional"))
      (node (ref "Y1") (pin "3") (pinfunction "3_3") (pintype "passive"))
    )
    (net (code "111") (name "VCC") (class "Default")
      (node (ref "C6") (pin "1") (pinfunction "1_1") (pintype "passive"))
      (node (ref "CAL1") (pin "E") (pinfunction "E_E") (pintype "passive"))
      (node (ref "CAL2") (pin "E") (pinfunction "E_E") (pintype "passive"))
      (node (ref "CAL3") (pin "E") (pinfunction "E_E") (pintype "passive"))
      (node (ref "CO2") (pin "3") (pinfunction "3_3") (pintype "passive"))
      (node (ref "IC1") (pin "8") (pinfunction "V+_8") (pintype "power_in"))
      (node (ref "IC2") (pin "8") (pinfunction "V+_8") (pintype "power_in"))
      (node (ref "IC3") (pin "4") (pinfunction "OUT_4") (pintype "passive"))
      (node (ref "IC4") (pin "16") (pinfunction "VCC_16") (pintype "power_in"))
      (node (ref "IC5") (pin "16") (pinfunction "VCC_16") (pintype "power_in"))
      (node (ref "IC6") (pin "16") (pinfunction "VCC_16") (pintype "power_in"))
      (node (ref "IC7") (pin "16") (pinfunction "VCC_16") (pintype "power_in"))
      (node (ref "ISP") (pin "2") (pinfunction "2_2") (pintype "passive"))
      (node (ref "Q2") (pin "2") (pinfunction "S_2") (pintype "passive"))
      (node (ref "Q3") (pin "2") (pinfunction "S_2") (pintype "passive"))
      (node (ref "Q4") (pin "2") (pinfunction "S_2") (pintype "passive"))
      (node (ref "Q5") (pin "2") (pinfunction "S_2") (pintype "passive"))
      (node (ref "R14") (pin "2") (pinfunction "2_2") (pintype "passive"))
      (node (ref "R28") (pin "2") (pinfunction "2_2") (pintype "passive"))
      (node (ref "R37") (pin "2") (pinfunction "2_2") (pintype "passive"))
      (node (ref "R46") (pin "2") (pinfunction "2_2") (pintype "passive"))
      (node (ref "R55") (pin "2") (pinfunction "2_2") (pintype "passive"))
      (node (ref "SER") (pin "3") (pinfunction "3_3") (pintype "passive"))
      (node (ref "U1") (pin "18") (pinfunction "AVCC_18") (pintype "bidirectional"))
      (node (ref "U1") (pin "4") (pinfunction "VCC_4") (pintype "bidirectional"))
      (node (ref "U1") (pin "6") (pinfunction "VCC_6") (pintype "bidirectional"))
    )
    (net (code "112") (name "unconnected-(GAIN_1-PadE)") (class "Default")
      (node (ref "GAIN_1") (pin "E") (pinfunction "E_E") (pintype "passive"))
    )
    (net (code "113") (name "unconnected-(GAIN_2-PadE)") (class "Default")
      (node (ref "GAIN_2") (pin "E") (pinfunction "E_E") (pintype "passive"))
    )
    (net (code "114") (name "unconnected-(GAIN_3-PadE)") (class "Default")
      (node (ref "GAIN_3") (pin "E") (pinfunction "E_E") (pintype "passive"))
    )
    (net (code "115") (name "unconnected-(IC7-QH*-Pad9)") (class "Default")
      (node (ref "IC7") (pin "9") (pinfunction "QH*_9") (pintype "tri_state"))
    )
    (net (code "116") (name "unconnected-(LED2-AP1-Pad10)") (class "Default")
      (node (ref "LED2") (pin "10") (pinfunction "AP1_10") (pintype "bidirectional"))
    )
    (net (code "117") (name "unconnected-(LED2-AP2-Pad9)") (class "Default")
      (node (ref "LED2") (pin "9") (pinfunction "AP2_9") (pintype "bidirectional"))
    )
    (net (code "118") (name "unconnected-(LED2-SC1-Pad4)") (class "Default")
      (node (ref "LED2") (pin "4") (pinfunction "SC1_4") (pintype "bidirectional"))
    )
    (net (code "119") (name "unconnected-(LED2-SC2-Pad12)") (class "Default")
      (node (ref "LED2") (pin "12") (pinfunction "SC2_12") (pintype "bidirectional"))
    )
    (net (code "120") (name "unconnected-(LED3-AP1-Pad10)") (class "Default")
      (node (ref "LED3") (pin "10") (pinfunction "AP1_10") (pintype "bidirectional"))
    )
    (net (code "121") (name "unconnected-(LED3-AP2-Pad9)") (class "Default")
      (node (ref "LED3") (pin "9") (pinfunction "AP2_9") (pintype "bidirectional"))
    )
    (net (code "122") (name "unconnected-(LED3-SC1-Pad4)") (class "Default")
      (node (ref "LED3") (pin "4") (pinfunction "SC1_4") (pintype "bidirectional"))
    )
    (net (code "123") (name "unconnected-(LED3-SC2-Pad12)") (class "Default")
      (node (ref "LED3") (pin "12") (pinfunction "SC2_12") (pintype "bidirectional"))
    )
    (net (code "124") (name "unconnected-(LED4-AP1-Pad10)") (class "Default")
      (node (ref "LED4") (pin "10") (pinfunction "AP1_10") (pintype "bidirectional"))
    )
    (net (code "125") (name "unconnected-(LED4-AP2-Pad9)") (class "Default")
      (node (ref "LED4") (pin "9") (pinfunction "AP2_9") (pintype "bidirectional"))
    )
    (net (code "126") (name "unconnected-(LED4-SC1-Pad4)") (class "Default")
      (node (ref "LED4") (pin "4") (pinfunction "SC1_4") (pintype "bidirectional"))
    )
    (net (code "127") (name "unconnected-(LED4-SC2-Pad12)") (class "Default")
      (node (ref "LED4") (pin "12") (pinfunction "SC2_12") (pintype "bidirectional"))
    )
    (net (code "128") (name "unconnected-(LED5-AP1-Pad10)") (class "Default")
      (node (ref "LED5") (pin "10") (pinfunction "AP1_10") (pintype "bidirectional"))
    )
    (net (code "129") (name "unconnected-(LED5-AP2-Pad9)") (class "Default")
      (node (ref "LED5") (pin "9") (pinfunction "AP2_9") (pintype "bidirectional"))
    )
    (net (code "130") (name "unconnected-(LED5-SC1-Pad4)") (class "Default")
      (node (ref "LED5") (pin "4") (pinfunction "SC1_4") (pintype "bidirectional"))
    )
    (net (code "131") (name "unconnected-(LED5-SC2-Pad12)") (class "Default")
      (node (ref "LED5") (pin "12") (pinfunction "SC2_12") (pintype "bidirectional"))
    )
    (net (code "132") (name "unconnected-(SER-Pad2)") (class "Default")
      (node (ref "SER") (pin "2") (pinfunction "2_2") (pintype "passive"))
    )
    (net (code "133") (name "unconnected-(U1-AREF-Pad20)") (class "Default")
      (node (ref "U1") (pin "20") (pinfunction "AREF_20") (pintype "bidirectional"))
    )
    (net (code "134") (name "unconnected-(U1-PC0(ADC0)-Pad23)") (class "Default")
      (node (ref "U1") (pin "23") (pinfunction "PC0(ADC0)_23") (pintype "bidirectional"))
    )
    (net (code "135") (name "unconnected-(U1-PC1(ADC1)-Pad24)") (class "Default")
      (node (ref "U1") (pin "24") (pinfunction "PC1(ADC1)_24") (pintype "bidirectional"))
    )
  )
)
